# DM1097_GPIOHDR.net
KiCad netlist of a schematic drawn in Altium Designer
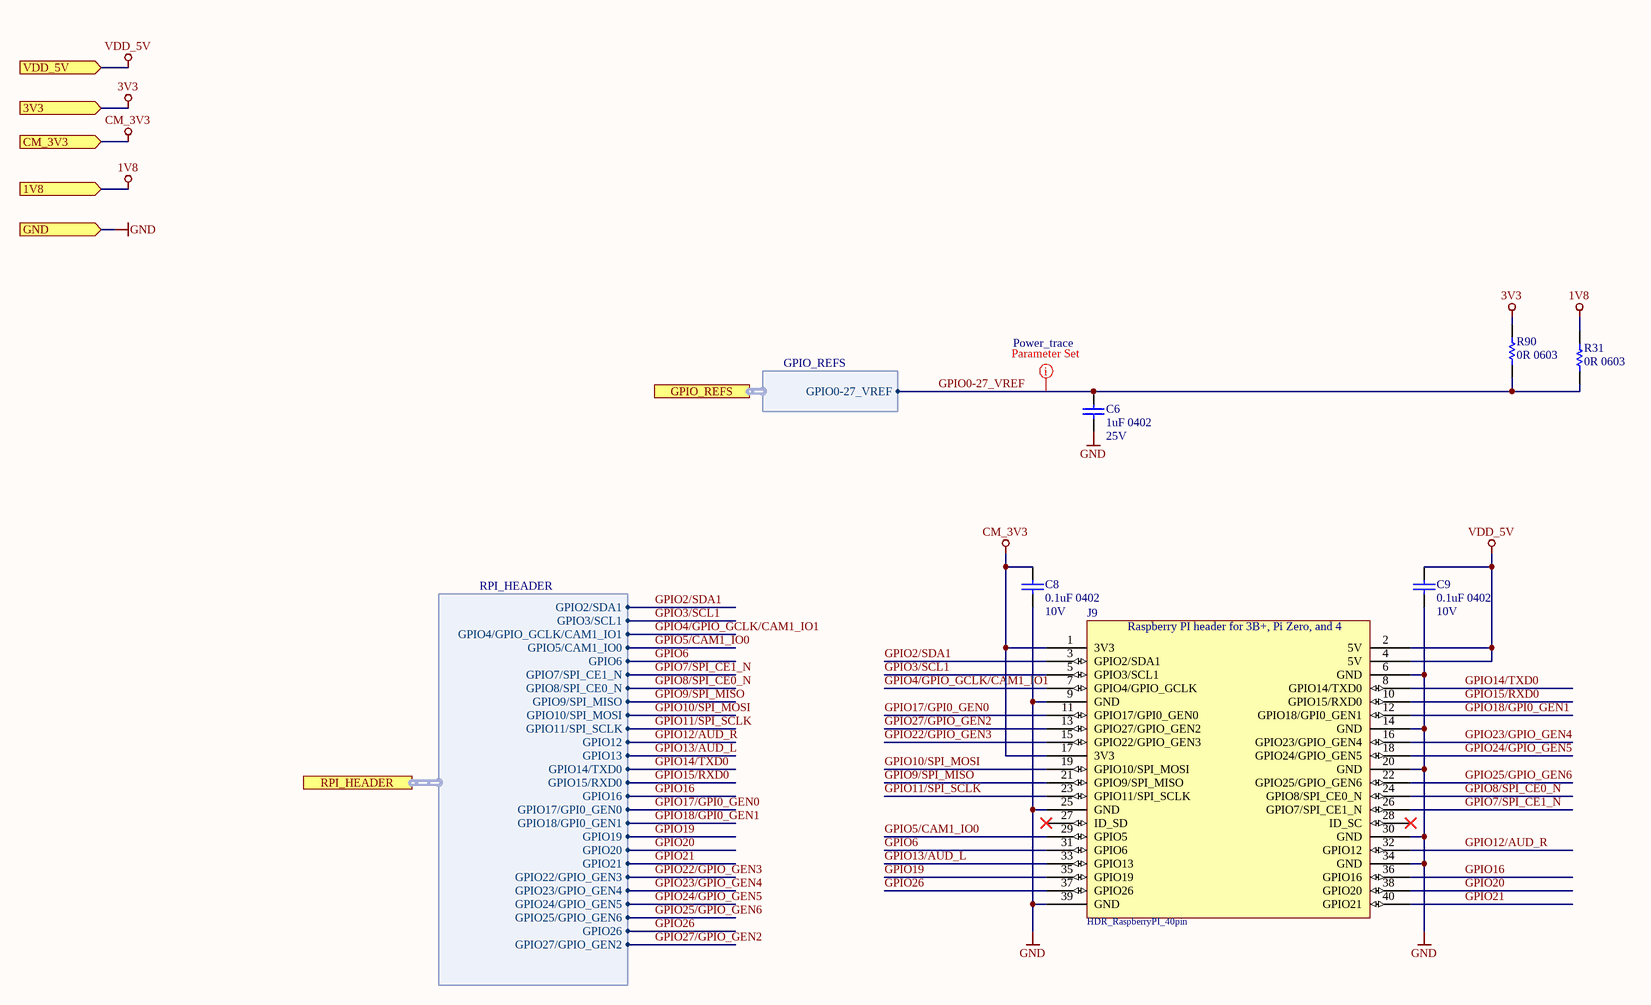
[diagram p0: DM1097_GPIOHDR.SchDoc]

(export (version "E")
  (design (tool "Eeschema 10.0.6"))
  (components
    (comp (ref "C6")
      (value "1uF 0402")
      (footprint "CAP_Altium_Vault_Generic:CAPC0402(1005)70_N")
      (description "CAP CER 1UF 25V X5R 0402 10%")
      (fields
        (field (name "TOLERANCE") "10%")
        (field (name "VOLTAGE") "25V")
        (field (name "VOLTAGE RATING") "25V")
      )
      (libsource (lib "LuxonisMaster") (part "GRM155R61E105KA12D"))
    )
    (comp (ref "C8")
      (value "0.1uF 0402")
      (footprint "CAP_Altium_Vault_Generic:CAPC0402(1005)70_N")
      (description "CAP CER 0.1UF 10V X7R 0402 5%")
      (fields (field (name "TOLERANCE") "5%") (field (name "VOLTAGE RATING") "10V"))
      (libsource (lib "LuxonisMaster") (part "GRM155R71A104JA01D"))
    )
    (comp (ref "C9")
      (value "0.1uF 0402")
      (footprint "CAP_Altium_Vault_Generic:CAPC0402(1005)70_N")
      (description "CAP CER 0.1UF 10V X7R 0402 5%")
      (fields (field (name "TOLERANCE") "5%") (field (name "VOLTAGE RATING") "10V"))
      (libsource (lib "LuxonisMaster") (part "GRM155R71A104JA01D"))
    )
    (comp (ref "J9")
      (value "HDR_RaspberryPI_40pin")
      (footprint "LuxonisMaster:61304021121")
      (description "CONN HEADER VERT 40POS 2.54MM THT HDR_RaspberryPI_40pin")
      (fields
        (field (name "MANUFACTURER") "Wurth Elektronik")
        (field (name "PART NUMBER") "61304021121")
        (field (name "PUBLISHER") "WurthElektronik")
      )
      (libsource (lib "LuxonisMaster") (part "61304021121_RPI_40pin"))
    )
    (comp (ref "R31")
      (value "0R 0603")
      (footprint "RES_Altium_Vault_Generic:RESC0603(1608)_N")
      (fields (field (name "TOLERANCE") "5%"))
      (libsource (lib "LuxonisMaster") (part "CRCW06030000Z0EA"))
    )
    (comp (ref "R90")
      (value "0R 0603")
      (footprint "RES_Altium_Vault_Generic:RESC0603(1608)_N")
      (fields (field (name "TOLERANCE") "5%"))
      (libsource (lib "LuxonisMaster") (part "CRCW06030000Z0EA"))
    )
  )
  (nets
    (net (code "3") (name "/GPIO0-27_VREF") (class "Default")
      (node (ref "C6") (pin "2") (pinfunction "2_2") (pintype "passive"))
      (node (ref "R31") (pin "1") (pinfunction "1_1") (pintype "passive"))
      (node (ref "R90") (pin "1") (pinfunction "1_1") (pintype "passive"))
    )
    (net (code "4") (name "/GPIO2{slash}SDA1") (class "Default")
      (node (ref "J9") (pin "3") (pinfunction "GPIO2/SDA1_3") (pintype "bidirectional"))
    )
    (net (code "5") (name "/GPIO3{slash}SCL1") (class "Default")
      (node (ref "J9") (pin "5") (pinfunction "GPIO3/SCL1_5") (pintype "bidirectional"))
    )
    (net (code "6") (name "/GPIO4{slash}GPIO_GCLK{slash}CAM1_IO1") (class "Default")
      (node (ref "J9") (pin "7") (pinfunction "GPIO4/GPIO_GCLK_7") (pintype "bidirectional"))
    )
    (net (code "7") (name "/GPIO5{slash}CAM1_IO0") (class "Default")
      (node (ref "J9") (pin "29") (pinfunction "GPIO5_29") (pintype "bidirectional"))
    )
    (net (code "8") (name "/GPIO6") (class "Default")
      (node (ref "J9") (pin "31") (pinfunction "GPIO6_31") (pintype "bidirectional"))
    )
    (net (code "9") (name "/GPIO7{slash}SPI_CE1_N") (class "Default")
      (node (ref "J9") (pin "26") (pinfunction "GPIO7/SPI_CE1_N_26") (pintype "bidirectional"))
    )
    (net (code "10") (name "/GPIO8{slash}SPI_CE0_N") (class "Default")
      (node (ref "J9") (pin "24") (pinfunction "GPIO8/SPI_CE0_N_24") (pintype "bidirectional"))
    )
    (net (code "11") (name "/GPIO9{slash}SPI_MISO") (class "Default")
      (node (ref "J9") (pin "21") (pinfunction "GPIO9/SPI_MISO_21") (pintype "bidirectional"))
    )
    (net (code "12") (name "/GPIO10{slash}SPI_MOSI") (class "Default")
      (node (ref "J9") (pin "19") (pinfunction "GPIO10/SPI_MOSI_19") (pintype "bidirectional"))
    )
    (net (code "13") (name "/GPIO11{slash}SPI_SCLK") (class "Default")
      (node (ref "J9") (pin "23") (pinfunction "GPIO11/SPI_SCLK_23") (pintype "bidirectional"))
    )
    (net (code "14") (name "/GPIO12{slash}AUD_R") (class "Default")
      (node (ref "J9") (pin "32") (pinfunction "GPIO12_32") (pintype "bidirectional"))
    )
    (net (code "15") (name "/GPIO13{slash}AUD_L") (class "Default")
      (node (ref "J9") (pin "33") (pinfunction "GPIO13_33") (pintype "bidirectional"))
    )
    (net (code "16") (name "/GPIO14{slash}TXD0") (class "Default")
      (node (ref "J9") (pin "8") (pinfunction "GPIO14/TXD0_8") (pintype "bidirectional"))
    )
    (net (code "17") (name "/GPIO15{slash}RXD0") (class "Default")
      (node (ref "J9") (pin "10") (pinfunction "GPIO15/RXD0_10") (pintype "bidirectional"))
    )
    (net (code "18") (name "/GPIO16") (class "Default")
      (node (ref "J9") (pin "36") (pinfunction "GPIO16_36") (pintype "bidirectional"))
    )
    (net (code "19") (name "/GPIO17{slash}GPI0_GEN0") (class "Default")
      (node (ref "J9") (pin "11") (pinfunction "GPIO17/GPI0_GEN0_11") (pintype "bidirectional"))
    )
    (net (code "20") (name "/GPIO18{slash}GPI0_GEN1") (class "Default")
      (node (ref "J9") (pin "12") (pinfunction "GPIO18/GPI0_GEN1_12") (pintype "bidirectional"))
    )
    (net (code "21") (name "/GPIO19") (class "Default")
      (node (ref "J9") (pin "35") (pinfunction "GPIO19_35") (pintype "bidirectional"))
    )
    (net (code "22") (name "/GPIO20") (class "Default")
      (node (ref "J9") (pin "38") (pinfunction "GPIO20_38") (pintype "bidirectional"))
    )
    (net (code "23") (name "/GPIO21") (class "Default")
      (node (ref "J9") (pin "40") (pinfunction "GPIO21_40") (pintype "bidirectional"))
    )
    (net (code "24") (name "/GPIO22{slash}GPIO_GEN3") (class "Default")
      (node (ref "J9") (pin "15") (pinfunction "GPIO22/GPIO_GEN3_15") (pintype "bidirectional"))
    )
    (net (code "25") (name "/GPIO23{slash}GPIO_GEN4") (class "Default")
      (node (ref "J9") (pin "16") (pinfunction "GPIO23/GPIO_GEN4_16") (pintype "bidirectional"))
    )
    (net (code "26") (name "/GPIO24{slash}GPIO_GEN5") (class "Default")
      (node (ref "J9") (pin "18") (pinfunction "GPIO24/GPIO_GEN5_18") (pintype "bidirectional"))
    )
    (net (code "27") (name "/GPIO25{slash}GPIO_GEN6") (class "Default")
      (node (ref "J9") (pin "22") (pinfunction "GPIO25/GPIO_GEN6_22") (pintype "bidirectional"))
    )
    (net (code "28") (name "/GPIO26") (class "Default")
      (node (ref "J9") (pin "37") (pinfunction "GPIO26_37") (pintype "bidirectional"))
    )
    (net (code "29") (name "/GPIO27{slash}GPIO_GEN2") (class "Default")
      (node (ref "J9") (pin "13") (pinfunction "GPIO27/GPIO_GEN2_13") (pintype "bidirectional"))
    )
    (net (code "32") (name "1V8") (class "Default")
      (node (ref "R31") (pin "2") (pinfunction "2_2") (pintype "passive"))
    )
    (net (code "33") (name "3V3") (class "Default")
      (node (ref "R90") (pin "2") (pinfunction "2_2") (pintype "passive"))
    )
    (net (code "34") (name "CM_3V3") (class "Default")
      (node (ref "C8") (pin "2") (pinfunction "2_2") (pintype "passive"))
      (node (ref "J9") (pin "1") (pinfunction "3V3_1") (pintype "passive"))
      (node (ref "J9") (pin "17") (pinfunction "3V3_17") (pintype "passive"))
    )
    (net (code "35") (name "GND") (class "Default")
      (node (ref "C6") (pin "1") (pinfunction "1_1") (pintype "passive"))
      (node (ref "C8") (pin "1") (pinfunction "1_1") (pintype "passive"))
      (node (ref "C9") (pin "1") (pinfunction "1_1") (pintype "passive"))
      (node (ref "J9") (pin "14") (pinfunction "GND_14") (pintype "passive"))
      (node (ref "J9") (pin "20") (pinfunction "GND_20") (pintype "passive"))
      (node (ref "J9") (pin "25") (pinfunction "GND_25") (pintype "passive"))
      (node (ref "J9") (pin "30") (pinfunction "GND_30") (pintype "passive"))
      (node (ref "J9") (pin "34") (pinfunction "GND_34") (pintype "passive"))
      (node (ref "J9") (pin "39") (pinfunction "GND_39") (pintype "passive"))
      (node (ref "J9") (pin "6") (pinfunction "GND_6") (pintype "passive"))
      (node (ref "J9") (pin "9") (pinfunction "GND_9") (pintype "passive"))
    )
    (net (code "36") (name "VDD_5V") (class "Default")
      (node (ref "C9") (pin "2") (pinfunction "2_2") (pintype "passive"))
      (node (ref "J9") (pin "2") (pinfunction "5V_2") (pintype "passive"))
      (node (ref "J9") (pin "4") (pinfunction "5V_4") (pintype "passive"))
    )
    (net (code "37") (name "unconnected-(J9-ID_SC-Pad28)") (class "Default")
      (node (ref "J9") (pin "28") (pinfunction "ID_SC_28") (pintype "bidirectional+no_connect"))
    )
    (net (code "38") (name "unconnected-(J9-ID_SD-Pad27)") (class "Default")
      (node (ref "J9") (pin "27") (pinfunction "ID_SD_27") (pintype "bidirectional+no_connect"))
    )
  )
)
